# controller.net
KiCad netlist of a schematic drawn in EAGLE
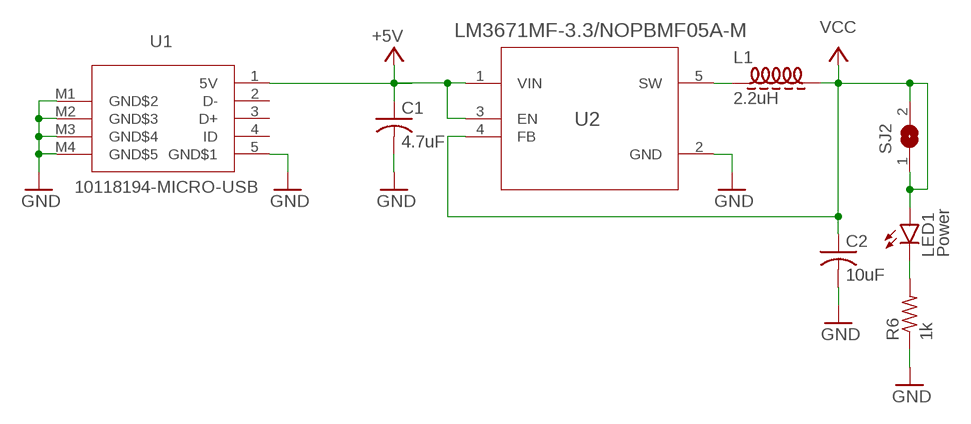
[diagram p0: schematic, sheet 1]
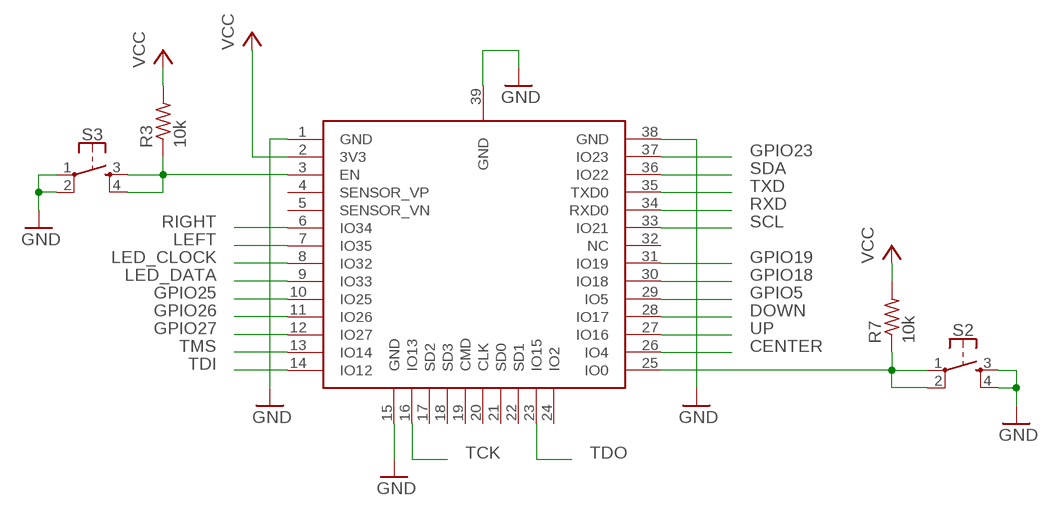
[diagram p1: schematic, sheet 2]
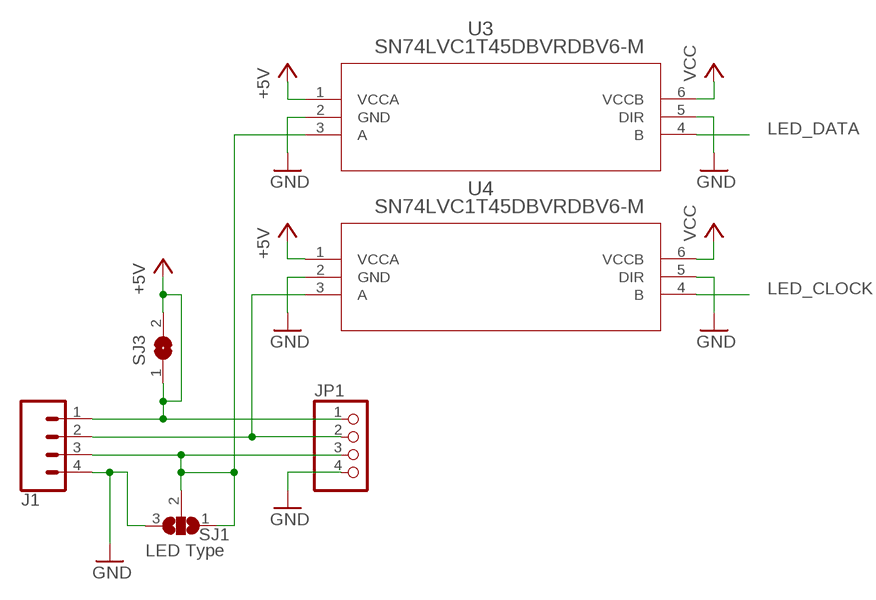
[diagram p2: schematic, sheet 3]
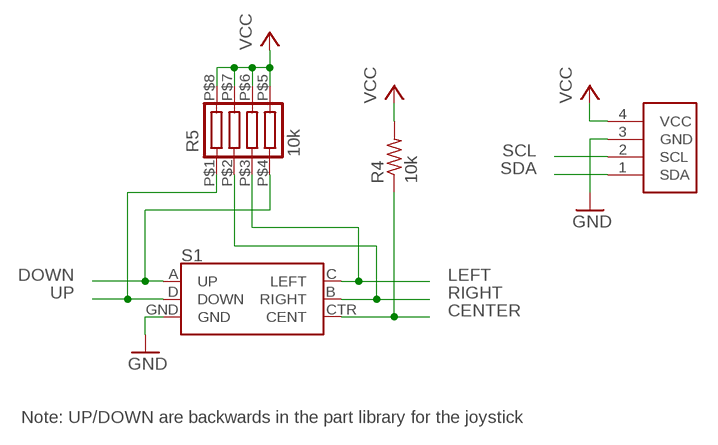
[diagram p3: schematic, sheet 4]
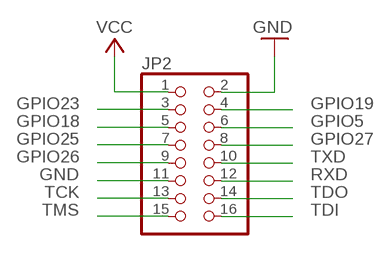
[diagram p4: schematic, sheet 5]

(export (version "E")
  (design (tool "Eeschema 10.0.6"))
  (components
    (comp (ref "J1")
      (value "CONN_04SCREW")
      (footprint "eagle-import:SCREWTERMINAL-3.5MM-4")
      (libsource (lib "eagle-import") (part "CONN_04SCREW"))
    )
    (comp (ref "JP1")
      (value "PINHD-1X4")
      (footprint "eagle-import:1X04")
      (libsource (lib "eagle-import") (part "PINHD-1X4"))
    )
    (comp (ref "SJ1")
      (value "LED Type")
      (footprint "eagle-import:SJ_2")
      (libsource (lib "eagle-import") (part "SJ2W"))
    )
    (comp (ref "SJ3") (value "SJ") (footprint "eagle-import:SJ") (libsource (lib "eagle-import") (part "SJ")))
    (comp (ref "U3")
      (value "SN74LVC1T45DBVRDBV6-M")
      (footprint "eagle-import:DBV6-M")
      (fields (field (name "MANUFACTURER_PART_NUMBER") "SN74LVC1T45DBVR"))
      (libsource (lib "eagle-import") (part "SN74LVC1T45DBVRDBV6-M"))
    )
    (comp (ref "U4")
      (value "SN74LVC1T45DBVRDBV6-M")
      (footprint "eagle-import:DBV6-M")
      (fields (field (name "MANUFACTURER_PART_NUMBER") "SN74LVC1T45DBVR"))
      (libsource (lib "eagle-import") (part "SN74LVC1T45DBVRDBV6-M"))
    )
    (comp (ref "R4")
      (value "10k")
      (footprint "eagle-import:R0805")
      (libsource (lib "eagle-import") (part "R-US_R0805"))
    )
    (comp (ref "R5")
      (value "10k")
      (footprint "eagle-import:2012-4N-CONCAVE")
      (libsource (lib "eagle-import") (part "744C083"))
    )
    (comp (ref "S1")
      (value "JOYSTICK_MINI")
      (footprint "eagle-import:JOYSTICK_MINI")
      (libsource (lib "eagle-import") (part "JOYSTICK_MINI"))
    )
    (comp (ref "U$5")
      (value "SSD1306-OLED")
      (footprint "eagle-import:SSD1306-OLED")
      (libsource (lib "eagle-import") (part "SSD1306-OLED"))
    )
    (comp (ref "C1")
      (value "4.7uF")
      (footprint "eagle-import:C0805")
      (libsource (lib "eagle-import") (part "C-USC0805"))
    )
    (comp (ref "C2")
      (value "10uF")
      (footprint "eagle-import:C0805")
      (libsource (lib "eagle-import") (part "C-USC0805"))
    )
    (comp (ref "L1")
      (value "2.2uH")
      (footprint "eagle-import:R0805")
      (libsource (lib "eagle-import") (part "IND-0805"))
    )
    (comp (ref "LED1")
      (value "Power")
      (footprint "eagle-import:CHIPLED_0805")
      (libsource (lib "eagle-import") (part "LEDCHIPLED_0805"))
    )
    (comp (ref "R6")
      (value "1k")
      (footprint "eagle-import:R0805")
      (libsource (lib "eagle-import") (part "R-US_R0805"))
    )
    (comp (ref "SJ2") (value "SJ") (footprint "eagle-import:SJ") (libsource (lib "eagle-import") (part "SJ")))
    (comp (ref "U1")
      (value "10118194-MICRO-USB")
      (footprint "eagle-import:10118194-MICRO-USB")
      (libsource (lib "eagle-import") (part "10118194-MICRO-USB"))
    )
    (comp (ref "U2")
      (value "LM3671MF-3.3/NOPBMF05A-M")
      (footprint "eagle-import:MF05A-M")
      (fields (field (name "MANUFACTURER_PART_NUMBER") "LM3671MF3.3NOPB"))
      (libsource (lib "eagle-import") (part "LM3671MF-3.3/NOPBMF05A-M"))
    )
    (comp (ref "R3")
      (value "10k")
      (footprint "eagle-import:R0805")
      (libsource (lib "eagle-import") (part "R-US_R0805"))
    )
    (comp (ref "R7")
      (value "10k")
      (footprint "eagle-import:R0805")
      (libsource (lib "eagle-import") (part "R-US_R0805"))
    )
    (comp (ref "S2")
      (value "MOMENTARY-SWITCH-SPST-2-SMD-4.6X2.8MM")
      (footprint "eagle-import:TACTILE_SWITCH_SMD_4.6X2.8MM")
      (libsource (lib "eagle-import") (part "MOMENTARY-SWITCH-SPST-2-SMD-4.6X2.8MM"))
    )
    (comp (ref "S3")
      (value "MOMENTARY-SWITCH-SPST-2-SMD-4.6X2.8MM")
      (footprint "eagle-import:TACTILE_SWITCH_SMD_4.6X2.8MM")
      (libsource (lib "eagle-import") (part "MOMENTARY-SWITCH-SPST-2-SMD-4.6X2.8MM"))
    )
    (comp (ref "U$2")
      (value "ESP32-WROOM-32D")
      (footprint "eagle-import:ESP32-WROOM-32D")
      (libsource (lib "eagle-import") (part "ESP32-WROOM-32D"))
    )
    (comp (ref "JP2")
      (value "PINHD-2X8")
      (footprint "eagle-import:2X08")
      (libsource (lib "eagle-import") (part "PINHD-2X8"))
    )
  )
  (nets
    (net (code "1") (name "+5V") (class "Default")
      (node (ref "C1") (pin "1") (pinfunction "1_1") (pintype "passive"))
      (node (ref "J1") (pin "1") (pinfunction "1_1") (pintype "passive"))
      (node (ref "JP1") (pin "1") (pinfunction "1_1") (pintype "passive"))
      (node (ref "SJ3") (pin "1") (pinfunction "1_1") (pintype "passive"))
      (node (ref "SJ3") (pin "2") (pinfunction "2_2") (pintype "passive"))
      (node (ref "U1") (pin "1") (pinfunction "5V_1") (pintype "bidirectional"))
      (node (ref "U2") (pin "1") (pinfunction "VIN_1") (pintype "input"))
      (node (ref "U2") (pin "3") (pinfunction "EN_3") (pintype "passive"))
      (node (ref "U3") (pin "1") (pinfunction "VCCA_1") (pintype "power_in"))
      (node (ref "U4") (pin "1") (pinfunction "VCCA_1") (pintype "power_in"))
    )
    (net (code "2") (name "CENTER") (class "Default")
      (node (ref "R4") (pin "1") (pinfunction "1_1") (pintype "passive"))
      (node (ref "S1") (pin "CTR") (pinfunction "CENT_CTR") (pintype "bidirectional"))
      (node (ref "U$2") (pin "26") (pinfunction "IO4_26") (pintype "bidirectional"))
    )
    (net (code "3") (name "DOWN") (class "Default")
      (node (ref "R5") (pin "P$4") (pinfunction "4_P$4") (pintype "passive"))
      (node (ref "S1") (pin "A") (pinfunction "UP_A") (pintype "bidirectional"))
      (node (ref "U$2") (pin "28") (pinfunction "IO17_28") (pintype "passive"))
    )
    (net (code "4") (name "GND") (class "Default")
      (node (ref "C1") (pin "2") (pinfunction "2_2") (pintype "passive"))
      (node (ref "C2") (pin "2") (pinfunction "2_2") (pintype "passive"))
      (node (ref "J1") (pin "4") (pinfunction "4_4") (pintype "passive"))
      (node (ref "JP1") (pin "4") (pinfunction "4_4") (pintype "passive"))
      (node (ref "JP2") (pin "11") (pinfunction "11_11") (pintype "passive"))
      (node (ref "JP2") (pin "2") (pinfunction "2_2") (pintype "passive"))
      (node (ref "R6") (pin "1") (pinfunction "1_1") (pintype "passive"))
      (node (ref "S1") (pin "GND") (pinfunction "GND_GND") (pintype "bidirectional"))
      (node (ref "S2") (pin "3") (pinfunction "3_3") (pintype "passive"))
      (node (ref "S2") (pin "4") (pinfunction "4_4") (pintype "passive"))
      (node (ref "S3") (pin "1") (pinfunction "1_1") (pintype "passive"))
      (node (ref "S3") (pin "2") (pinfunction "2_2") (pintype "passive"))
      (node (ref "SJ1") (pin "3") (pinfunction "3_3") (pintype "passive"))
      (node (ref "U$2") (pin "1") (pinfunction "GND_1") (pintype "passive"))
      (node (ref "U$2") (pin "15") (pinfunction "GND_15") (pintype "passive"))
      (node (ref "U$2") (pin "38") (pinfunction "GND_38") (pintype "passive"))
      (node (ref "U$2") (pin "39") (pinfunction "GND_39") (pintype "bidirectional"))
      (node (ref "U$5") (pin "3") (pinfunction "GND_3") (pintype "power_in"))
      (node (ref "U1") (pin "5") (pinfunction "GND$1_5") (pintype "bidirectional"))
      (node (ref "U1") (pin "M1") (pinfunction "GND$2_M1") (pintype "passive"))
      (node (ref "U1") (pin "M2") (pinfunction "GND$3_M2") (pintype "passive"))
      (node (ref "U1") (pin "M3") (pinfunction "GND$4_M3") (pintype "passive"))
      (node (ref "U1") (pin "M4") (pinfunction "GND$5_M4") (pintype "passive"))
      (node (ref "U2") (pin "2") (pinfunction "GND_2") (pintype "passive"))
      (node (ref "U3") (pin "2") (pinfunction "GND_2") (pintype "power_in"))
      (node (ref "U3") (pin "5") (pinfunction "DIR_5") (pintype "input"))
      (node (ref "U4") (pin "2") (pinfunction "GND_2") (pintype "power_in"))
      (node (ref "U4") (pin "5") (pinfunction "DIR_5") (pintype "input"))
    )
    (net (code "5") (name "GPIO5") (class "Default")
      (node (ref "JP2") (pin "6") (pinfunction "6_6") (pintype "passive"))
      (node (ref "U$2") (pin "29") (pinfunction "IO5_29") (pintype "passive"))
    )
    (net (code "6") (name "GPIO18") (class "Default")
      (node (ref "JP2") (pin "5") (pinfunction "5_5") (pintype "passive"))
      (node (ref "U$2") (pin "30") (pinfunction "IO18_30") (pintype "passive"))
    )
    (net (code "7") (name "GPIO19") (class "Default")
      (node (ref "JP2") (pin "4") (pinfunction "4_4") (pintype "passive"))
      (node (ref "U$2") (pin "31") (pinfunction "IO19_31") (pintype "passive"))
    )
    (net (code "8") (name "GPIO23") (class "Default")
      (node (ref "JP2") (pin "3") (pinfunction "3_3") (pintype "passive"))
      (node (ref "U$2") (pin "37") (pinfunction "IO23_37") (pintype "passive"))
    )
    (net (code "9") (name "GPIO25") (class "Default")
      (node (ref "JP2") (pin "7") (pinfunction "7_7") (pintype "passive"))
      (node (ref "U$2") (pin "10") (pinfunction "IO25_10") (pintype "passive"))
    )
    (net (code "10") (name "GPIO26") (class "Default")
      (node (ref "JP2") (pin "9") (pinfunction "9_9") (pintype "passive"))
      (node (ref "U$2") (pin "11") (pinfunction "IO26_11") (pintype "passive"))
    )
    (net (code "11") (name "GPIO27") (class "Default")
      (node (ref "JP2") (pin "8") (pinfunction "8_8") (pintype "passive"))
      (node (ref "U$2") (pin "12") (pinfunction "IO27_12") (pintype "bidirectional"))
    )
    (net (code "12") (name "LED_CLOCK") (class "Default")
      (node (ref "U$2") (pin "8") (pinfunction "IO32_8") (pintype "passive"))
      (node (ref "U4") (pin "4") (pinfunction "B_4") (pintype "input"))
    )
    (net (code "13") (name "LED_DATA") (class "Default")
      (node (ref "U$2") (pin "9") (pinfunction "IO33_9") (pintype "passive"))
      (node (ref "U3") (pin "4") (pinfunction "B_4") (pintype "input"))
    )
    (net (code "14") (name "LEFT") (class "Default")
      (node (ref "R5") (pin "P$3") (pinfunction "3_P$3") (pintype "passive"))
      (node (ref "S1") (pin "C") (pinfunction "LEFT_C") (pintype "bidirectional"))
      (node (ref "U$2") (pin "7") (pinfunction "IO35_7") (pintype "passive"))
    )
    (net (code "15") (name "Net-(LED1-PadC)") (class "Default")
      (node (ref "LED1") (pin "C") (pinfunction "C_C") (pintype "passive"))
      (node (ref "R6") (pin "2") (pinfunction "2_2") (pintype "passive"))
    )
    (net (code "16") (name "Net-(U$2-EN)") (class "Default")
      (node (ref "R3") (pin "1") (pinfunction "1_1") (pintype "passive"))
      (node (ref "S3") (pin "3") (pinfunction "3_3") (pintype "passive"))
      (node (ref "S3") (pin "4") (pinfunction "4_4") (pintype "passive"))
      (node (ref "U$2") (pin "3") (pinfunction "EN_3") (pintype "passive"))
    )
    (net (code "17") (name "Net-(U$2-IO0)") (class "Default")
      (node (ref "R7") (pin "1") (pinfunction "1_1") (pintype "passive"))
      (node (ref "S2") (pin "1") (pinfunction "1_1") (pintype "passive"))
      (node (ref "S2") (pin "2") (pinfunction "2_2") (pintype "passive"))
      (node (ref "U$2") (pin "25") (pinfunction "IO0_25") (pintype "bidirectional"))
    )
    (net (code "18") (name "Net-(U2-SW)") (class "Default")
      (node (ref "L1") (pin "1") (pinfunction "1_1") (pintype "passive"))
      (node (ref "U2") (pin "5") (pinfunction "SW_5") (pintype "output"))
    )
    (net (code "19") (name "Net-(U3-A)") (class "Default")
      (node (ref "J1") (pin "3") (pinfunction "3_3") (pintype "passive"))
      (node (ref "JP1") (pin "3") (pinfunction "3_3") (pintype "passive"))
      (node (ref "SJ1") (pin "1") (pinfunction "1_1") (pintype "passive"))
      (node (ref "SJ1") (pin "2") (pinfunction "2_2") (pintype "passive"))
      (node (ref "U3") (pin "3") (pinfunction "A_3") (pintype "input"))
    )
    (net (code "20") (name "Net-(U4-A)") (class "Default")
      (node (ref "J1") (pin "2") (pinfunction "2_2") (pintype "passive"))
      (node (ref "JP1") (pin "2") (pinfunction "2_2") (pintype "passive"))
      (node (ref "U4") (pin "3") (pinfunction "A_3") (pintype "input"))
    )
    (net (code "21") (name "RIGHT") (class "Default")
      (node (ref "R5") (pin "P$2") (pinfunction "2_P$2") (pintype "passive"))
      (node (ref "S1") (pin "B") (pinfunction "RIGHT_B") (pintype "bidirectional"))
      (node (ref "U$2") (pin "6") (pinfunction "IO34_6") (pintype "passive"))
    )
    (net (code "22") (name "RXD") (class "Default")
      (node (ref "JP2") (pin "12") (pinfunction "12_12") (pintype "passive"))
      (node (ref "U$2") (pin "34") (pinfunction "RXD0_34") (pintype "passive"))
    )
    (net (code "23") (name "SCL") (class "Default")
      (node (ref "U$2") (pin "33") (pinfunction "IO21_33") (pintype "passive"))
      (node (ref "U$5") (pin "2") (pinfunction "SCL_2") (pintype "passive"))
    )
    (net (code "24") (name "SDA") (class "Default")
      (node (ref "U$2") (pin "36") (pinfunction "IO22_36") (pintype "passive"))
      (node (ref "U$5") (pin "1") (pinfunction "SDA_1") (pintype "passive"))
    )
    (net (code "25") (name "TCK") (class "Default")
      (node (ref "JP2") (pin "13") (pinfunction "13_13") (pintype "passive"))
      (node (ref "U$2") (pin "16") (pinfunction "IO13_16") (pintype "passive"))
    )
    (net (code "26") (name "TDI") (class "Default")
      (node (ref "JP2") (pin "16") (pinfunction "16_16") (pintype "passive"))
      (node (ref "U$2") (pin "14") (pinfunction "IO12_14") (pintype "bidirectional"))
    )
    (net (code "27") (name "TDO") (class "Default")
      (node (ref "JP2") (pin "14") (pinfunction "14_14") (pintype "passive"))
      (node (ref "U$2") (pin "23") (pinfunction "IO15_23") (pintype "passive"))
    )
    (net (code "28") (name "TMS") (class "Default")
      (node (ref "JP2") (pin "15") (pinfunction "15_15") (pintype "passive"))
      (node (ref "U$2") (pin "13") (pinfunction "IO14_13") (pintype "bidirectional"))
    )
    (net (code "29") (name "TXD") (class "Default")
      (node (ref "JP2") (pin "10") (pinfunction "10_10") (pintype "passive"))
      (node (ref "U$2") (pin "35") (pinfunction "TXD0_35") (pintype "passive"))
    )
    (net (code "30") (name "UP") (class "Default")
      (node (ref "R5") (pin "P$1") (pinfunction "1_P$1") (pintype "passive"))
      (node (ref "S1") (pin "D") (pinfunction "DOWN_D") (pintype "bidirectional"))
      (node (ref "U$2") (pin "27") (pinfunction "IO16_27") (pintype "bidirectional"))
    )
    (net (code "31") (name "VCC") (class "Default")
      (node (ref "C2") (pin "1") (pinfunction "1_1") (pintype "passive"))
      (node (ref "JP2") (pin "1") (pinfunction "1_1") (pintype "passive"))
      (node (ref "L1") (pin "2") (pinfunction "2_2") (pintype "passive"))
      (node (ref "LED1") (pin "A") (pinfunction "A_A") (pintype "passive"))
      (node (ref "R3") (pin "2") (pinfunction "2_2") (pintype "passive"))
      (node (ref "R4") (pin "2") (pinfunction "2_2") (pintype "passive"))
      (node (ref "R5") (pin "P$5") (pinfunction "5_P$5") (pintype "passive"))
      (node (ref "R5") (pin "P$6") (pinfunction "6_P$6") (pintype "passive"))
      (node (ref "R5") (pin "P$7") (pinfunction "7_P$7") (pintype "passive"))
      (node (ref "R5") (pin "P$8") (pinfunction "8_P$8") (pintype "passive"))
      (node (ref "R7") (pin "2") (pinfunction "2_2") (pintype "passive"))
      (node (ref "SJ2") (pin "1") (pinfunction "1_1") (pintype "passive"))
      (node (ref "SJ2") (pin "2") (pinfunction "2_2") (pintype "passive"))
      (node (ref "U$2") (pin "2") (pinfunction "3V3_2") (pintype "passive"))
      (node (ref "U$5") (pin "4") (pinfunction "VCC_4") (pintype "power_in"))
      (node (ref "U2") (pin "4") (pinfunction "FB_4") (pintype "passive"))
      (node (ref "U3") (pin "6") (pinfunction "VCCB_6") (pintype "power_in"))
      (node (ref "U4") (pin "6") (pinfunction "VCCB_6") (pintype "power_in"))
    )
    (net (code "32") (name "unconnected-(U$2-CLK-Pad20)") (class "Default")
      (node (ref "U$2") (pin "20") (pinfunction "CLK_20") (pintype "no_connect"))
    )
    (net (code "33") (name "unconnected-(U$2-CMD-Pad19)") (class "Default")
      (node (ref "U$2") (pin "19") (pinfunction "CMD_19") (pintype "no_connect"))
    )
    (net (code "34") (name "unconnected-(U$2-IO2-Pad24)") (class "Default")
      (node (ref "U$2") (pin "24") (pinfunction "IO2_24") (pintype "passive"))
    )
    (net (code "35") (name "unconnected-(U$2-NC-Pad32)") (class "Default")
      (node (ref "U$2") (pin "32") (pinfunction "NC_32") (pintype "no_connect"))
    )
    (net (code "36") (name "unconnected-(U$2-SD0-Pad21)") (class "Default")
      (node (ref "U$2") (pin "21") (pinfunction "SD0_21") (pintype "no_connect"))
    )
    (net (code "37") (name "unconnected-(U$2-SD1-Pad22)") (class "Default")
      (node (ref "U$2") (pin "22") (pinfunction "SD1_22") (pintype "no_connect"))
    )
    (net (code "38") (name "unconnected-(U$2-SD2-Pad17)") (class "Default")
      (node (ref "U$2") (pin "17") (pinfunction "SD2_17") (pintype "no_connect"))
    )
    (net (code "39") (name "unconnected-(U$2-SD3-Pad18)") (class "Default")
      (node (ref "U$2") (pin "18") (pinfunction "SD3_18") (pintype "no_connect"))
    )
    (net (code "40") (name "unconnected-(U$2-SENSOR_VN-Pad5)") (class "Default")
      (node (ref "U$2") (pin "5") (pinfunction "SENSOR_VN_5") (pintype "passive"))
    )
    (net (code "41") (name "unconnected-(U$2-SENSOR_VP-Pad4)") (class "Default")
      (node (ref "U$2") (pin "4") (pinfunction "SENSOR_VP_4") (pintype "passive"))
    )
    (net (code "42") (name "unconnected-(U1-D+-Pad3)") (class "Default")
      (node (ref "U1") (pin "3") (pinfunction "D+_3") (pintype "bidirectional"))
    )
    (net (code "43") (name "unconnected-(U1-D--Pad2)") (class "Default")
      (node (ref "U1") (pin "2") (pinfunction "D-_2") (pintype "bidirectional"))
    )
    (net (code "44") (name "unconnected-(U1-ID-Pad4)") (class "Default")
      (node (ref "U1") (pin "4") (pinfunction "ID_4") (pintype "bidirectional"))
    )
  )
)
